# 01_PowerSupply.net
KiCad netlist of a schematic drawn in Altium Designer
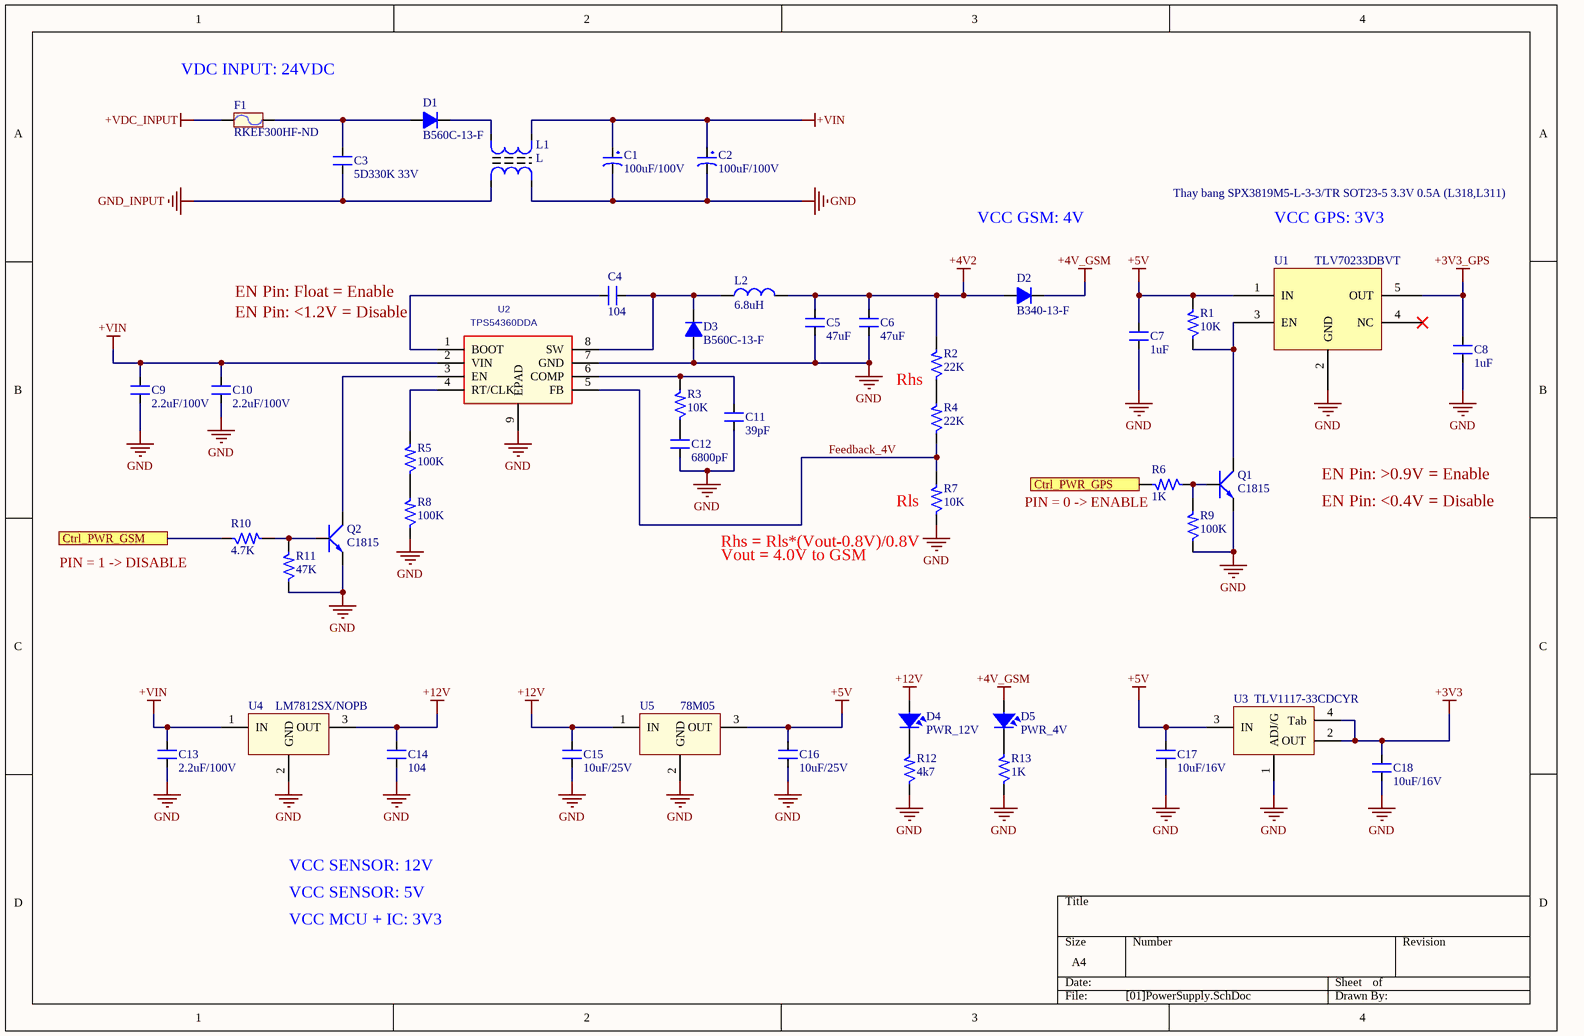
[diagram p0: [01]PowerSupply.SchDoc]

(export (version "E")
  (design (tool "Eeschema 10.0.6"))
  (components
    (comp (ref "C1")
      (value "100uF/100V")
      (footprint "CP1.5/3.4")
      (description "Cap 100uF/35V - 470uF/16V")
      (libsource (lib "syhaunguyen") (part "CP3"))
    )
    (comp (ref "C2")
      (value "100uF/100V")
      (footprint "CP1.5/3.4")
      (description "Cap 100uF/35V - 470uF/16V")
      (libsource (lib "syhaunguyen") (part "CP3"))
    )
    (comp (ref "C3")
      (value "5D330K 33V")
      (footprint "CN2")
      (fields (field (name "DESIGNED BY") "VanDungEvn"))
      (libsource (lib "GPS_Traking_V1_1") (part "CN"))
    )
    (comp (ref "C4")
      (value "104")
      (footprint "CAP_0603")
      (description "Cap SMD")
      (libsource (lib "GPS_Traking_V1_1") (part "CM_1"))
    )
    (comp (ref "C5")
      (value "47uF")
      (footprint "SM-1210")
      (description "Cap SMD")
      (libsource (lib "GPS_Traking_V1_1") (part "CM_1"))
    )
    (comp (ref "C6")
      (value "47uF")
      (footprint "SM-1210")
      (description "Cap SMD")
      (libsource (lib "GPS_Traking_V1_1") (part "CM_1"))
    )
    (comp (ref "C7")
      (value "1uF")
      (footprint "CAP_0805")
      (description "Cap SMD")
      (libsource (lib "GPS_Traking_V1_1") (part "CM_1"))
    )
    (comp (ref "C8")
      (value "1uF")
      (footprint "CAP_0805")
      (description "Cap SMD")
      (libsource (lib "GPS_Traking_V1_1") (part "CM_1"))
    )
    (comp (ref "C9")
      (value "2.2uF/100V")
      (footprint "SM-1210")
      (description "CAP CER 2.2UF 100V X7R 1210  445-4498-2-ND")
      (libsource (lib "GPS_Traking_V1_1") (part "CM"))
    )
    (comp (ref "C10")
      (value "2.2uF/100V")
      (footprint "SM-1210")
      (description "CAP CER 2.2UF 100V X7R 1210  445-4498-2-ND")
      (libsource (lib "GPS_Traking_V1_1") (part "CM"))
    )
    (comp (ref "C11")
      (value "39pF")
      (footprint "CAP_0805")
      (description "Cap SMD")
      (libsource (lib "GPS_Traking_V1_1") (part "CM_1"))
    )
    (comp (ref "C12")
      (value "6800pF")
      (footprint "CAP_0805")
      (description "Cap SMD")
      (libsource (lib "GPS_Traking_V1_1") (part "CM_1"))
    )
    (comp (ref "C13")
      (value "2.2uF/100V")
      (footprint "SM-1210")
      (description "CAP CER 2.2UF 100V X7R 1210  445-4498-2-ND")
      (libsource (lib "GPS_Traking_V1_1") (part "CM"))
    )
    (comp (ref "C14")
      (value "104")
      (footprint "CAP_0805")
      (description "Cap SMD")
      (libsource (lib "GPS_Traking_V1_1") (part "CM_1"))
    )
    (comp (ref "C15")
      (value "10uF/25V")
      (footprint "CAP_0805")
      (description "Cap SMD")
      (libsource (lib "GPS_Traking_V1_1") (part "CM_1"))
    )
    (comp (ref "C16")
      (value "10uF/25V")
      (footprint "CAP_0805")
      (description "Cap SMD")
      (libsource (lib "GPS_Traking_V1_1") (part "CM_1"))
    )
    (comp (ref "C17")
      (value "10uF/16V")
      (footprint "CAP_0805")
      (description "Cap SMD")
      (libsource (lib "GPS_Traking_V1_1") (part "CM_1"))
    )
    (comp (ref "C18")
      (value "10uF/16V")
      (footprint "CAP_0805")
      (description "Cap SMD")
      (libsource (lib "GPS_Traking_V1_1") (part "CM_1"))
    )
    (comp (ref "D1")
      (value "B560C-13-F")
      (footprint "DO-214AB SMC")
      (description "DIODE SCHOTTKY 60V 5A SMC")
      (libsource (lib "GPS_Traking_V1_1") (part "D5A"))
    )
    (comp (ref "D2")
      (value "B340-13-F")
      (footprint "DO-214AB SMA")
      (description "DIODE SCHOTTKY 40V 3A SMC")
      (libsource (lib "GPS_Traking_V1_1") (part "D1A"))
    )
    (comp (ref "D3")
      (value "B560C-13-F")
      (footprint "DO-214AB SMC")
      (description "DIODE SCHOTTKY 60V 5A SMC")
      (libsource (lib "GPS_Traking_V1_1") (part "D5A"))
    )
    (comp (ref "D4")
      (value "PWR_12V")
      (footprint "LED-0805-Yellow")
      (description "LED Single colour Green and Red")
      (libsource (lib "GPS_Traking_V1_1") (part "LED"))
    )
    (comp (ref "D5")
      (value "PWR_4V")
      (footprint "LED-0805-Green")
      (description "LED Single colour Green and Red")
      (libsource (lib "GPS_Traking_V1_1") (part "LED"))
    )
    (comp (ref "F1")
      (value "RKEF300HF-ND")
      (footprint "FUSE2")
      (description "PTC RESET FUSE 60V 3A RADIAL")
      (fields (field (name "DESIGNED BY") "VanDungEvn"))
      (libsource (lib "GPS_Traking_V1_1") (part "Fuse"))
    )
    (comp (ref "L1")
      (value "L")
      (footprint "L2 UF9.8")
      (description "Inductor")
      (fields (field (name "DESIGNED BY") "VanDungEvn"))
      (libsource (lib "GPS_Traking_V1_1") (part "L2x220"))
    )
    (comp (ref "L2")
      (value "6.8uH")
      (footprint "L01 SMD 12*12*6")
      (description "FIXED IND 6.2UH 5.7A 22.4 MOHM")
      (libsource (lib "GPS_Traking_V1_1") (part "L1"))
    )
    (comp (ref "Q1")
      (value "C1815")
      (footprint "SOT23B")
      (description "NPN 600mW, ECB")
      (libsource (lib "GPS_Traking_V1_1") (part "C1815"))
    )
    (comp (ref "Q2")
      (value "C1815")
      (footprint "SOT23B")
      (description "NPN 600mW, ECB")
      (libsource (lib "GPS_Traking_V1_1") (part "C1815"))
    )
    (comp (ref "R1")
      (value "10K")
      (footprint "RES-SMD-0805")
      (description "Resistor SMD")
      (libsource (lib "GPS_Traking_V1_1") (part "RM"))
    )
    (comp (ref "R2")
      (value "22K")
      (footprint "RES-SMD-0805")
      (description "Resistor SMD")
      (libsource (lib "GPS_Traking_V1_1") (part "RM"))
    )
    (comp (ref "R3")
      (value "10K")
      (footprint "RES-SMD-0805")
      (description "Resistor SMD")
      (libsource (lib "GPS_Traking_V1_1") (part "RM"))
    )
    (comp (ref "R4")
      (value "22K")
      (footprint "RES-SMD-0805")
      (description "Resistor SMD")
      (libsource (lib "GPS_Traking_V1_1") (part "RM"))
    )
    (comp (ref "R5")
      (value "100K")
      (footprint "RES-SMD-0805")
      (description "Resistor SMD")
      (libsource (lib "GPS_Traking_V1_1") (part "RM"))
    )
    (comp (ref "R6")
      (value "1K")
      (footprint "RES-SMD-0805")
      (description "Resistor SMD")
      (libsource (lib "GPS_Traking_V1_1") (part "RM"))
    )
    (comp (ref "R7")
      (value "10K")
      (footprint "RES-SMD-0805")
      (description "Resistor SMD")
      (libsource (lib "GPS_Traking_V1_1") (part "RM"))
    )
    (comp (ref "R8")
      (value "100K")
      (footprint "RES-SMD-0805")
      (description "Resistor SMD")
      (libsource (lib "GPS_Traking_V1_1") (part "RM"))
    )
    (comp (ref "R9")
      (value "100K")
      (footprint "RES-SMD-0805")
      (description "Resistor SMD")
      (libsource (lib "GPS_Traking_V1_1") (part "RM"))
    )
    (comp (ref "R10")
      (value "4.7K")
      (footprint "RES-SMD-0805")
      (description "Resistor SMD")
      (libsource (lib "GPS_Traking_V1_1") (part "RM"))
    )
    (comp (ref "R11")
      (value "47K")
      (footprint "RES-SMD-0805")
      (description "Resistor SMD")
      (libsource (lib "GPS_Traking_V1_1") (part "RM"))
    )
    (comp (ref "R12")
      (value "4k7")
      (footprint "RES-SMD-0805")
      (description "Resistor SMD")
      (libsource (lib "GPS_Traking_V1_1") (part "RM"))
    )
    (comp (ref "R13")
      (value "1K")
      (footprint "RES-SMD-0805")
      (description "Resistor SMD")
      (libsource (lib "GPS_Traking_V1_1") (part "RM"))
    )
    (comp (ref "U1")
      (value "TLV70233DBVT")
      (footprint "TLV70233_3.3V")
      (libsource (lib "GPS_Traking_V1_1") (part "TLV70233_3.3V"))
    )
    (comp (ref "U2")
      (value "TPS54360DDA")
      (footprint "DDA8_3P1X2P4-M")
      (description "REG BUCK SPLIT RAIL 8SOPWRPAD")
      (libsource (lib "GPS_Traking_V1_1") (part "TPS54360DDA"))
    )
    (comp (ref "U3")
      (value "TLV1117-33CDCYR")
      (footprint "SOT223-4N")
      (description "3v3")
      (libsource (lib "GPS_Traking_V1_1") (part "LM1117"))
    )
    (comp (ref "U4")
      (value "LM7812SX/NOPB")
      (footprint "TO-263-4")
      (libsource (lib "GPS_Traking_V1_1") (part "LM78xx_1"))
    )
    (comp (ref "U5")
      (value "78M05")
      (footprint "TO252-3L")
      (description "On ap +, from + 5 to + 24VDC")
      (libsource (lib "GPS_Traking_V1_1") (part "LM78xx"))
    )
  )
  (nets
    (net (code "1") (name "+3V3") (class "Default")
      (node (ref "C18") (pin "2") (pinfunction "2_2") (pintype "passive"))
      (node (ref "U3") (pin "2") (pinfunction "OUT_2") (pintype "passive"))
      (node (ref "U3") (pin "4") (pinfunction "Tab_4") (pintype "passive"))
    )
    (net (code "2") (name "+3V3_GPS") (class "Default")
      (node (ref "C8") (pin "2") (pinfunction "2_2") (pintype "passive"))
      (node (ref "U1") (pin "5") (pinfunction "OUT_5") (pintype "passive"))
    )
    (net (code "3") (name "+4V2") (class "Default")
      (node (ref "C5") (pin "2") (pinfunction "2_2") (pintype "passive"))
      (node (ref "C6") (pin "2") (pinfunction "2_2") (pintype "passive"))
      (node (ref "D2") (pin "1") (pinfunction "A_1") (pintype "passive"))
      (node (ref "L2") (pin "2") (pinfunction "2_2") (pintype "passive"))
      (node (ref "R2") (pin "2") (pinfunction "2_2") (pintype "passive"))
    )
    (net (code "4") (name "+4V_GSM") (class "Default")
      (node (ref "D2") (pin "2") (pinfunction "K_2") (pintype "passive"))
      (node (ref "D5") (pin "1") (pinfunction "1_1") (pintype "passive"))
    )
    (net (code "5") (name "+5V") (class "Default")
      (node (ref "C16") (pin "2") (pinfunction "2_2") (pintype "passive"))
      (node (ref "C17") (pin "2") (pinfunction "2_2") (pintype "passive"))
      (node (ref "C7") (pin "2") (pinfunction "2_2") (pintype "passive"))
      (node (ref "R1") (pin "2") (pinfunction "2_2") (pintype "passive"))
      (node (ref "U1") (pin "1") (pinfunction "IN_1") (pintype "passive"))
      (node (ref "U3") (pin "3") (pinfunction "IN_3") (pintype "passive"))
      (node (ref "U5") (pin "3") (pinfunction "OUT_3") (pintype "passive"))
    )
    (net (code "6") (name "+12V") (class "Default")
      (node (ref "C14") (pin "2") (pinfunction "2_2") (pintype "passive"))
      (node (ref "C15") (pin "2") (pinfunction "2_2") (pintype "passive"))
      (node (ref "D4") (pin "1") (pinfunction "1_1") (pintype "passive"))
      (node (ref "U4") (pin "3") (pinfunction "OUT_3") (pintype "passive"))
      (node (ref "U5") (pin "1") (pinfunction "IN_1") (pintype "passive"))
    )
    (net (code "7") (name "+VDC_INPUT") (class "Default")
      (node (ref "F1") (pin "1") (pinfunction "1_1") (pintype "passive"))
    )
    (net (code "8") (name "+VIN") (class "Default")
      (node (ref "C1") (pin "1") (pinfunction "1_1") (pintype "passive"))
      (node (ref "C10") (pin "2") (pinfunction "2_2") (pintype "passive"))
      (node (ref "C13") (pin "2") (pinfunction "2_2") (pintype "passive"))
      (node (ref "C2") (pin "1") (pinfunction "1_1") (pintype "passive"))
      (node (ref "C9") (pin "2") (pinfunction "2_2") (pintype "passive"))
      (node (ref "L1") (pin "3") (pinfunction "3_3") (pintype "passive"))
      (node (ref "U2") (pin "2") (pinfunction "VIN_2") (pintype "passive"))
      (node (ref "U4") (pin "1") (pinfunction "IN_1") (pintype "passive"))
    )
    (net (code "9") (name "/Ctrl_PWR_GPS") (class "Default")
      (node (ref "R6") (pin "2") (pinfunction "2_2") (pintype "passive"))
    )
    (net (code "10") (name "/Ctrl_PWR_GSM") (class "Default")
      (node (ref "R10") (pin "1") (pinfunction "1_1") (pintype "passive"))
    )
    (net (code "11") (name "/Feedback_4V") (class "Default")
      (node (ref "R4") (pin "1") (pinfunction "1_1") (pintype "passive"))
      (node (ref "R7") (pin "2") (pinfunction "2_2") (pintype "passive"))
      (node (ref "U2") (pin "5") (pinfunction "FB_5") (pintype "passive"))
    )
    (net (code "12") (name "GND") (class "Default")
      (node (ref "C1") (pin "2") (pinfunction "2_2") (pintype "passive"))
      (node (ref "C10") (pin "1") (pinfunction "1_1") (pintype "passive"))
      (node (ref "C11") (pin "1") (pinfunction "1_1") (pintype "passive"))
      (node (ref "C12") (pin "1") (pinfunction "1_1") (pintype "passive"))
      (node (ref "C13") (pin "1") (pinfunction "1_1") (pintype "passive"))
      (node (ref "C14") (pin "1") (pinfunction "1_1") (pintype "passive"))
      (node (ref "C15") (pin "1") (pinfunction "1_1") (pintype "passive"))
      (node (ref "C16") (pin "1") (pinfunction "1_1") (pintype "passive"))
      (node (ref "C17") (pin "1") (pinfunction "1_1") (pintype "passive"))
      (node (ref "C18") (pin "1") (pinfunction "1_1") (pintype "passive"))
      (node (ref "C2") (pin "2") (pinfunction "2_2") (pintype "passive"))
      (node (ref "C5") (pin "1") (pinfunction "1_1") (pintype "passive"))
      (node (ref "C6") (pin "1") (pinfunction "1_1") (pintype "passive"))
      (node (ref "C7") (pin "1") (pinfunction "1_1") (pintype "passive"))
      (node (ref "C8") (pin "1") (pinfunction "1_1") (pintype "passive"))
      (node (ref "C9") (pin "1") (pinfunction "1_1") (pintype "passive"))
      (node (ref "D3") (pin "1") (pinfunction "A_1") (pintype "passive"))
      (node (ref "L1") (pin "2") (pinfunction "2_2") (pintype "passive"))
      (node (ref "Q1") (pin "1") (pinfunction "E_1") (pintype "passive"))
      (node (ref "Q2") (pin "1") (pinfunction "E_1") (pintype "passive"))
      (node (ref "R11") (pin "1") (pinfunction "1_1") (pintype "passive"))
      (node (ref "R12") (pin "1") (pinfunction "1_1") (pintype "passive"))
      (node (ref "R13") (pin "1") (pinfunction "1_1") (pintype "passive"))
      (node (ref "R7") (pin "1") (pinfunction "1_1") (pintype "passive"))
      (node (ref "R8") (pin "1") (pinfunction "1_1") (pintype "passive"))
      (node (ref "R9") (pin "1") (pinfunction "1_1") (pintype "passive"))
      (node (ref "U1") (pin "2") (pinfunction "GND_2") (pintype "power_in"))
      (node (ref "U2") (pin "7") (pinfunction "GND_7") (pintype "passive"))
      (node (ref "U2") (pin "9") (pinfunction "EPAD_9") (pintype "passive"))
      (node (ref "U3") (pin "1") (pinfunction "ADJ/G_1") (pintype "passive"))
      (node (ref "U4") (pin "2") (pinfunction "GND_2") (pintype "passive"))
      (node (ref "U5") (pin "2") (pinfunction "GND_2") (pintype "passive"))
    )
    (net (code "13") (name "GND_INPUT") (class "Default")
      (node (ref "C3") (pin "1") (pinfunction "1_1") (pintype "passive"))
      (node (ref "L1") (pin "1") (pinfunction "1_1") (pintype "passive"))
    )
    (net (code "14") (name "Net-(C12-Pad2)") (class "Default")
      (node (ref "C12") (pin "2") (pinfunction "2_2") (pintype "passive"))
      (node (ref "R3") (pin "1") (pinfunction "1_1") (pintype "passive"))
    )
    (net (code "15") (name "Net-(D1-A)") (class "Default")
      (node (ref "C3") (pin "2") (pinfunction "2_2") (pintype "passive"))
      (node (ref "D1") (pin "1") (pinfunction "A_1") (pintype "passive"))
      (node (ref "F1") (pin "2") (pinfunction "2_2") (pintype "passive"))
    )
    (net (code "16") (name "Net-(D1-K)") (class "Default")
      (node (ref "D1") (pin "2") (pinfunction "K_2") (pintype "passive"))
      (node (ref "L1") (pin "4") (pinfunction "4_4") (pintype "passive"))
    )
    (net (code "17") (name "Net-(D3-K)") (class "Default")
      (node (ref "C4") (pin "2") (pinfunction "2_2") (pintype "passive"))
      (node (ref "D3") (pin "2") (pinfunction "K_2") (pintype "passive"))
      (node (ref "L2") (pin "1") (pinfunction "1_1") (pintype "passive"))
      (node (ref "U2") (pin "8") (pinfunction "SW_8") (pintype "passive"))
    )
    (net (code "18") (name "Net-(D4-Pad2)") (class "Default")
      (node (ref "D4") (pin "2") (pinfunction "2_2") (pintype "passive"))
      (node (ref "R12") (pin "2") (pinfunction "2_2") (pintype "passive"))
    )
    (net (code "19") (name "Net-(D5-Pad2)") (class "Default")
      (node (ref "D5") (pin "2") (pinfunction "2_2") (pintype "passive"))
      (node (ref "R13") (pin "2") (pinfunction "2_2") (pintype "passive"))
    )
    (net (code "20") (name "Net-(Q1-B)") (class "Default")
      (node (ref "Q1") (pin "3") (pinfunction "B_3") (pintype "passive"))
      (node (ref "R6") (pin "1") (pinfunction "1_1") (pintype "passive"))
      (node (ref "R9") (pin "2") (pinfunction "2_2") (pintype "passive"))
    )
    (net (code "21") (name "Net-(Q1-C)") (class "Default")
      (node (ref "Q1") (pin "2") (pinfunction "C_2") (pintype "passive"))
      (node (ref "R1") (pin "1") (pinfunction "1_1") (pintype "passive"))
      (node (ref "U1") (pin "3") (pinfunction "EN_3") (pintype "passive"))
    )
    (net (code "22") (name "Net-(Q2-B)") (class "Default")
      (node (ref "Q2") (pin "3") (pinfunction "B_3") (pintype "passive"))
      (node (ref "R10") (pin "2") (pinfunction "2_2") (pintype "passive"))
      (node (ref "R11") (pin "2") (pinfunction "2_2") (pintype "passive"))
    )
    (net (code "23") (name "Net-(Q2-C)") (class "Default")
      (node (ref "Q2") (pin "2") (pinfunction "C_2") (pintype "passive"))
      (node (ref "U2") (pin "3") (pinfunction "EN_3") (pintype "passive"))
    )
    (net (code "24") (name "Net-(R2-Pad1)") (class "Default")
      (node (ref "R2") (pin "1") (pinfunction "1_1") (pintype "passive"))
      (node (ref "R4") (pin "2") (pinfunction "2_2") (pintype "passive"))
    )
    (net (code "25") (name "Net-(R5-Pad1)") (class "Default")
      (node (ref "R5") (pin "1") (pinfunction "1_1") (pintype "passive"))
      (node (ref "R8") (pin "2") (pinfunction "2_2") (pintype "passive"))
    )
    (net (code "26") (name "Net-(U2-BOOT)") (class "Default")
      (node (ref "C4") (pin "1") (pinfunction "1_1") (pintype "passive"))
      (node (ref "U2") (pin "1") (pinfunction "BOOT_1") (pintype "passive"))
    )
    (net (code "27") (name "Net-(U2-COMP)") (class "Default")
      (node (ref "C11") (pin "2") (pinfunction "2_2") (pintype "passive"))
      (node (ref "R3") (pin "2") (pinfunction "2_2") (pintype "passive"))
      (node (ref "U2") (pin "6") (pinfunction "COMP_6") (pintype "passive"))
    )
    (net (code "28") (name "Net-(U2-RT{slash}CLK)") (class "Default")
      (node (ref "R5") (pin "2") (pinfunction "2_2") (pintype "passive"))
      (node (ref "U2") (pin "4") (pinfunction "RT/CLK_4") (pintype "passive"))
    )
    (net (code "29") (name "unconnected-(U1-NC-Pad4)") (class "Default")
      (node (ref "U1") (pin "4") (pinfunction "NC_4") (pintype "passive+no_connect"))
    )
  )
)
